# Super-Regenerative-VHF-KosmosX3000.net
KiCad netlist of a schematic drawn in EAGLE
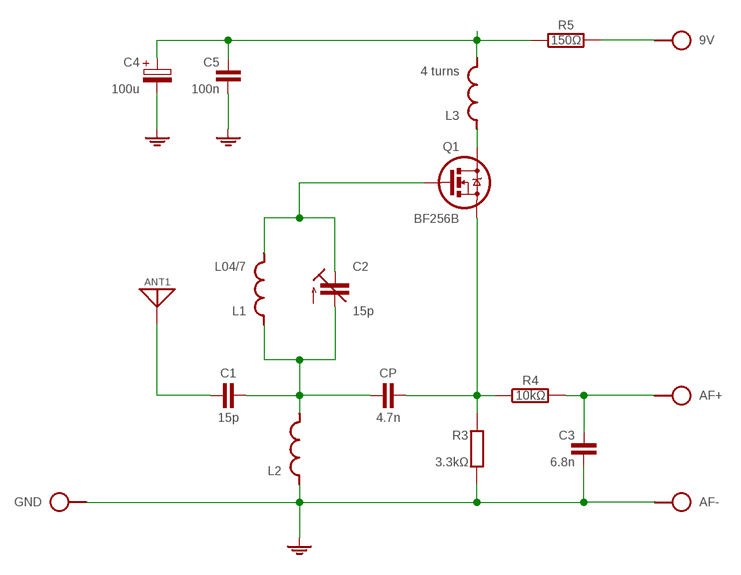
[diagram p0: schematic, sheet 1]

(export (version "E")
  (design (tool "Eeschema 10.0.6"))
  (components
    (comp (ref "9V")
      (value "SPAD")
      (footprint "eagle-import:SPAD@1")
      (libsource (lib "eagle-import") (part "SPAD"))
    )
    (comp (ref "AF+")
      (value "SPAD")
      (footprint "eagle-import:SPAD@1")
      (libsource (lib "eagle-import") (part "SPAD"))
    )
    (comp (ref "AF-")
      (value "SPAD")
      (footprint "eagle-import:SPAD@1")
      (libsource (lib "eagle-import") (part "SPAD"))
    )
    (comp (ref "ANT1")
      (value "ANT")
      (footprint "eagle-import:SPAD")
      (libsource (lib "eagle-import") (part "ANT"))
    )
    (comp (ref "C1")
      (value "15p")
      (footprint "eagle-import:C025-015X024")
      (libsource (lib "eagle-import") (part "C025-015X024"))
    )
    (comp (ref "C2")
      (value "15p")
      (footprint "eagle-import:TRIM-2222-808")
      (libsource (lib "eagle-import") (part "C-TR-PH201272222-808-2PINB"))
    )
    (comp (ref "C3")
      (value "6.8n")
      (footprint "eagle-import:C050-020X036")
      (libsource (lib "eagle-import") (part "C050-020X036"))
    )
    (comp (ref "C4")
      (value "100u")
      (footprint "eagle-import:E2.5-4_V")
      (libsource (lib "eagle-import") (part "CPOLE2,5-4/V"))
    )
    (comp (ref "C5")
      (value "100n")
      (footprint "eagle-import:C025-015X024")
      (libsource (lib "eagle-import") (part "C025-015X024"))
    )
    (comp (ref "CP")
      (value "4.7n")
      (footprint "eagle-import:C050-020X036_V")
      (libsource (lib "eagle-import") (part "C050-020X036/V"))
    )
    (comp (ref "GND")
      (value "SPAD")
      (footprint "eagle-import:SPAD@1")
      (libsource (lib "eagle-import") (part "SPAD"))
    )
    (comp (ref "L1")
      (value "L04/7")
      (footprint "eagle-import:L-04-5_6V-C")
      (libsource (lib "eagle-import") (part "L-SHORT04-5/5V-C"))
    )
    (comp (ref "L2")
      (value "L-SHORT03/10")
      (footprint "eagle-import:L-03_10")
      (libsource (lib "eagle-import") (part "L-SHORT03/10"))
    )
    (comp (ref "L3")
      (value "4 turns")
      (footprint "eagle-import:L-04-5_6V-C")
      (libsource (lib "eagle-import") (part "L-SHORT04-5/5V-C"))
    )
    (comp (ref "Q1")
      (value "BF256B")
      (footprint "eagle-import:TO92")
      (libsource (lib "eagle-import") (part "BF256B"))
    )
    (comp (ref "R3")
      (value "3.3kΩ")
      (footprint "eagle-import:0204_10")
      (libsource (lib "eagle-import") (part "R0204/10"))
    )
    (comp (ref "R4")
      (value "10kΩ")
      (footprint "eagle-import:0202_10")
      (libsource (lib "eagle-import") (part "R-H0202/10"))
    )
    (comp (ref "R5")
      (value "150Ω")
      (footprint "eagle-import:0202_10")
      (libsource (lib "eagle-import") (part "R-H0202/10"))
    )
  )
  (nets
    (net (code "1") (name "GND") (class "Default")
      (node (ref "AF-") (pin "1") (pinfunction "P$1_1") (pintype "bidirectional"))
      (node (ref "C3") (pin "2") (pinfunction "2_2") (pintype "passive"))
      (node (ref "C4") (pin "-") (pinfunction "-_-") (pintype "passive"))
      (node (ref "C5") (pin "2") (pinfunction "2_2") (pintype "passive"))
      (node (ref "GND") (pin "1") (pinfunction "P$1_1") (pintype "bidirectional"))
      (node (ref "L2") (pin "2") (pinfunction "2_2") (pintype "passive"))
      (node (ref "R3") (pin "2") (pinfunction "1_2") (pintype "passive"))
    )
    (net (code "2") (name "Net-(9V-P$1)") (class "Default")
      (node (ref "9V") (pin "1") (pinfunction "P$1_1") (pintype "bidirectional"))
      (node (ref "R5") (pin "2") (pinfunction "2_2") (pintype "passive"))
    )
    (net (code "3") (name "Net-(AF+-P$1)") (class "Default")
      (node (ref "AF+") (pin "1") (pinfunction "P$1_1") (pintype "bidirectional"))
      (node (ref "C3") (pin "1") (pinfunction "1_1") (pintype "passive"))
      (node (ref "R4") (pin "2") (pinfunction "2_2") (pintype "passive"))
    )
    (net (code "4") (name "Net-(ANT1-Pad1)") (class "Default")
      (node (ref "ANT1") (pin "1") (pinfunction "1_1") (pintype "output"))
      (node (ref "C1") (pin "2") (pinfunction "2_2") (pintype "passive"))
    )
    (net (code "5") (name "Net-(C2-A)") (class "Default")
      (node (ref "C1") (pin "1") (pinfunction "1_1") (pintype "passive"))
      (node (ref "C2") (pin "2") (pinfunction "A_2") (pintype "passive"))
      (node (ref "CP") (pin "2") (pinfunction "2_2") (pintype "passive"))
      (node (ref "L1") (pin "2") (pinfunction "2_2") (pintype "passive"))
      (node (ref "L2") (pin "1") (pinfunction "1_1") (pintype "passive"))
    )
    (net (code "6") (name "Net-(C2-E)") (class "Default")
      (node (ref "C2") (pin "3") (pinfunction "E_3") (pintype "passive"))
      (node (ref "L1") (pin "1") (pinfunction "1_1") (pintype "passive"))
      (node (ref "Q1") (pin "1") (pinfunction "G_1") (pintype "passive"))
    )
    (net (code "7") (name "Net-(C4-Pad+)") (class "Default")
      (node (ref "C4") (pin "+") (pinfunction "+_+") (pintype "passive"))
      (node (ref "C5") (pin "1") (pinfunction "1_1") (pintype "passive"))
      (node (ref "L3") (pin "1") (pinfunction "1_1") (pintype "passive"))
      (node (ref "R5") (pin "1") (pinfunction "1_1") (pintype "passive"))
    )
    (net (code "8") (name "Net-(Q1-D)") (class "Default")
      (node (ref "L3") (pin "2") (pinfunction "2_2") (pintype "passive"))
      (node (ref "Q1") (pin "3") (pinfunction "D_3") (pintype "passive"))
    )
    (net (code "9") (name "Net-(Q1-S)") (class "Default")
      (node (ref "CP") (pin "1") (pinfunction "1_1") (pintype "passive"))
      (node (ref "Q1") (pin "2") (pinfunction "S_2") (pintype "passive"))
      (node (ref "R3") (pin "1") (pinfunction "2_1") (pintype "passive"))
      (node (ref "R4") (pin "1") (pinfunction "1_1") (pintype "passive"))
    )
  )
)
